# TriangleGenerator.net
KiCad netlist of a schematic drawn in EAGLE
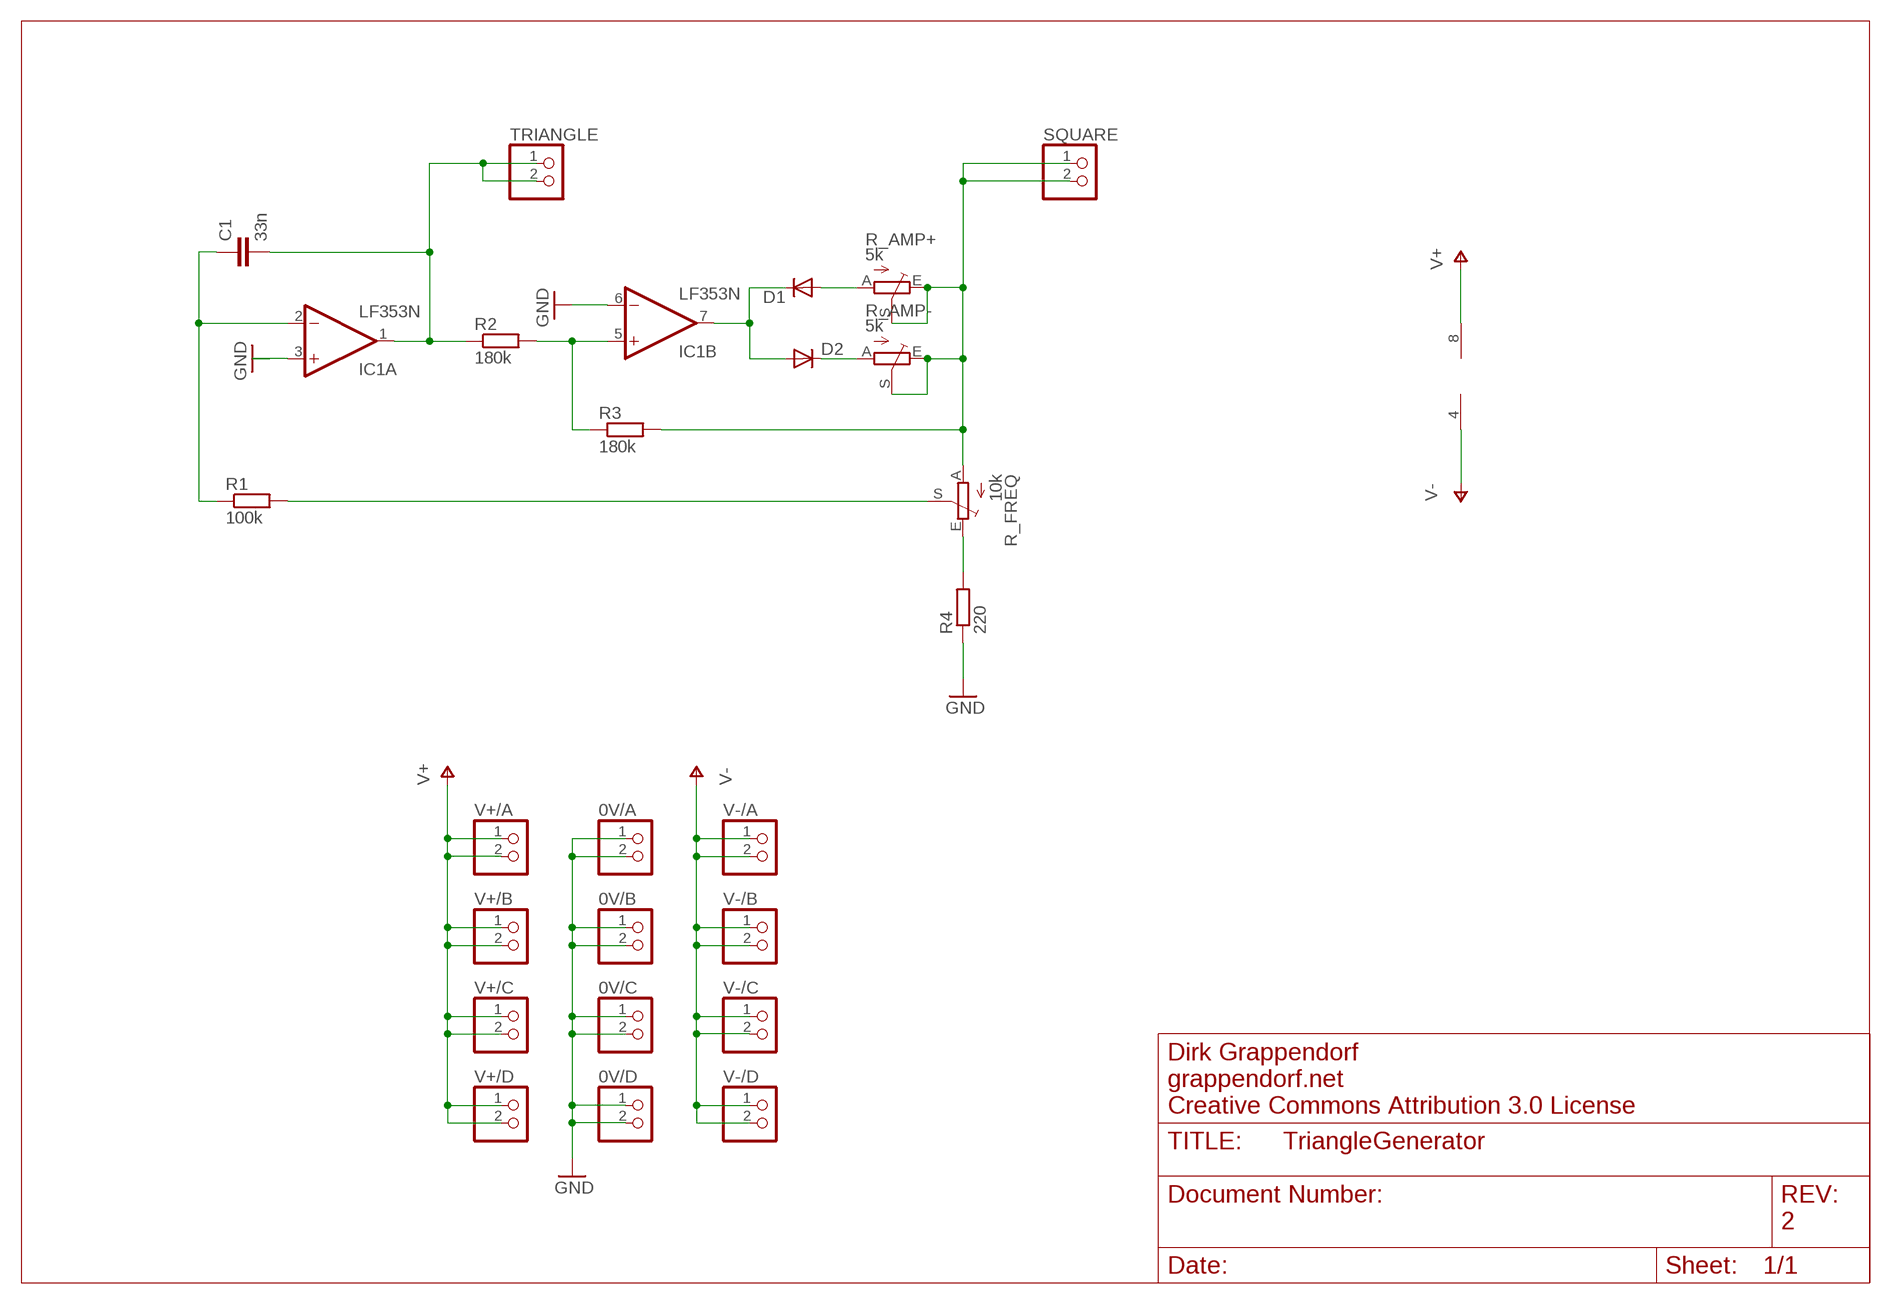
[diagram p0: schematic, sheet 1]

(export (version "E")
  (design (tool "Eeschema 10.0.6"))
  (components
    (comp (ref "0V/A")
      (value "PINHD-1X2")
      (footprint "eagle-import:1X02")
      (libsource (lib "eagle-import") (part "PINHD-1X2"))
    )
    (comp (ref "0V/B")
      (value "PINHD-1X2")
      (footprint "eagle-import:1X02")
      (libsource (lib "eagle-import") (part "PINHD-1X2"))
    )
    (comp (ref "0V/C")
      (value "PINHD-1X2")
      (footprint "eagle-import:1X02")
      (libsource (lib "eagle-import") (part "PINHD-1X2"))
    )
    (comp (ref "0V/D")
      (value "PINHD-1X2")
      (footprint "eagle-import:1X02")
      (libsource (lib "eagle-import") (part "PINHD-1X2"))
    )
    (comp (ref "C1")
      (value "33n")
      (footprint "eagle-import:C025-025X050")
      (libsource (lib "eagle-import") (part "C-EU025-025X050"))
    )
    (comp (ref "D1")
      (value "DIODE1N4148")
      (footprint "eagle-import:DIODE-1N4148")
      (libsource (lib "eagle-import") (part "DIODE1N4148"))
    )
    (comp (ref "D2")
      (value "DIODE1N4148")
      (footprint "eagle-import:DIODE-1N4148")
      (libsource (lib "eagle-import") (part "DIODE1N4148"))
    )
    (comp (ref "IC1")
      (value "LF353N")
      (footprint "eagle-import:DIL08")
      (libsource (lib "eagle-import") (part "LF353N"))
    )
    (comp (ref "R1")
      (value "100k")
      (footprint "eagle-import:0207_7")
      (libsource (lib "eagle-import") (part "R-EU_0207/7"))
    )
    (comp (ref "R2")
      (value "180k")
      (footprint "eagle-import:0207_7")
      (libsource (lib "eagle-import") (part "R-EU_0207/7"))
    )
    (comp (ref "R3")
      (value "180k")
      (footprint "eagle-import:0207_7")
      (libsource (lib "eagle-import") (part "R-EU_0207/7"))
    )
    (comp (ref "R4")
      (value "220")
      (footprint "eagle-import:0207_7")
      (libsource (lib "eagle-import") (part "R-EU_0207/7"))
    )
    (comp (ref "R_AMP+")
      (value "5k")
      (footprint "eagle-import:LI15")
      (libsource (lib "eagle-import") (part "TRIM_EU-LI15"))
    )
    (comp (ref "R_AMP-")
      (value "5k")
      (footprint "eagle-import:LI15")
      (libsource (lib "eagle-import") (part "TRIM_EU-LI15"))
    )
    (comp (ref "R_FREQ")
      (value "10k")
      (footprint "eagle-import:LI15")
      (libsource (lib "eagle-import") (part "TRIM_EU-LI15"))
    )
    (comp (ref "SQUARE")
      (value "PINHD-1X2")
      (footprint "eagle-import:1X02")
      (libsource (lib "eagle-import") (part "PINHD-1X2"))
    )
    (comp (ref "TRIANGLE")
      (value "PINHD-1X2")
      (footprint "eagle-import:1X02")
      (libsource (lib "eagle-import") (part "PINHD-1X2"))
    )
    (comp (ref "V+/A")
      (value "PINHD-1X2")
      (footprint "eagle-import:1X02")
      (libsource (lib "eagle-import") (part "PINHD-1X2"))
    )
    (comp (ref "V+/B")
      (value "PINHD-1X2")
      (footprint "eagle-import:1X02")
      (libsource (lib "eagle-import") (part "PINHD-1X2"))
    )
    (comp (ref "V+/C")
      (value "PINHD-1X2")
      (footprint "eagle-import:1X02")
      (libsource (lib "eagle-import") (part "PINHD-1X2"))
    )
    (comp (ref "V+/D")
      (value "PINHD-1X2")
      (footprint "eagle-import:1X02")
      (libsource (lib "eagle-import") (part "PINHD-1X2"))
    )
    (comp (ref "V-/A")
      (value "PINHD-1X2")
      (footprint "eagle-import:1X02")
      (libsource (lib "eagle-import") (part "PINHD-1X2"))
    )
    (comp (ref "V-/B")
      (value "PINHD-1X2")
      (footprint "eagle-import:1X02")
      (libsource (lib "eagle-import") (part "PINHD-1X2"))
    )
    (comp (ref "V-/C")
      (value "PINHD-1X2")
      (footprint "eagle-import:1X02")
      (libsource (lib "eagle-import") (part "PINHD-1X2"))
    )
    (comp (ref "V-/D")
      (value "PINHD-1X2")
      (footprint "eagle-import:1X02")
      (libsource (lib "eagle-import") (part "PINHD-1X2"))
    )
  )
  (nets
    (net (code "1") (name "GND") (class "Default")
      (node (ref "0V/A") (pin "1") (pinfunction "1_1") (pintype "passive"))
      (node (ref "0V/A") (pin "2") (pinfunction "2_2") (pintype "passive"))
      (node (ref "0V/B") (pin "1") (pinfunction "1_1") (pintype "passive"))
      (node (ref "0V/B") (pin "2") (pinfunction "2_2") (pintype "passive"))
      (node (ref "0V/C") (pin "1") (pinfunction "1_1") (pintype "passive"))
      (node (ref "0V/C") (pin "2") (pinfunction "2_2") (pintype "passive"))
      (node (ref "0V/D") (pin "1") (pinfunction "1_1") (pintype "passive"))
      (node (ref "0V/D") (pin "2") (pinfunction "2_2") (pintype "passive"))
      (node (ref "IC1") (pin "3") (pinfunction "+IN_3") (pintype "input"))
      (node (ref "IC1") (pin "6") (pinfunction "-IN_6") (pintype "input"))
      (node (ref "R4") (pin "1") (pinfunction "1_1") (pintype "passive"))
    )
    (net (code "2") (name "Net-(D1-PadA)") (class "Default")
      (node (ref "D1") (pin "A") (pinfunction "A_A") (pintype "passive"))
      (node (ref "R_AMP+") (pin "A") (pinfunction "A_A") (pintype "passive"))
    )
    (net (code "3") (name "Net-(D2-PadC)") (class "Default")
      (node (ref "D2") (pin "C") (pinfunction "C_C") (pintype "passive"))
      (node (ref "R_AMP-") (pin "A") (pinfunction "A_A") (pintype "passive"))
    )
    (net (code "4") (name "Net-(IC1A--IN)") (class "Default")
      (node (ref "C1") (pin "1") (pinfunction "1_1") (pintype "passive"))
      (node (ref "IC1") (pin "2") (pinfunction "-IN_2") (pintype "input"))
      (node (ref "R1") (pin "1") (pinfunction "1_1") (pintype "passive"))
    )
    (net (code "5") (name "Net-(IC1A-OUT)") (class "Default")
      (node (ref "C1") (pin "2") (pinfunction "2_2") (pintype "passive"))
      (node (ref "IC1") (pin "1") (pinfunction "OUT_1") (pintype "output"))
      (node (ref "R2") (pin "1") (pinfunction "1_1") (pintype "passive"))
      (node (ref "TRIANGLE") (pin "1") (pinfunction "1_1") (pintype "passive"))
      (node (ref "TRIANGLE") (pin "2") (pinfunction "2_2") (pintype "passive"))
    )
    (net (code "6") (name "Net-(IC1B-+IN)") (class "Default")
      (node (ref "IC1") (pin "5") (pinfunction "+IN_5") (pintype "input"))
      (node (ref "R2") (pin "2") (pinfunction "2_2") (pintype "passive"))
      (node (ref "R3") (pin "1") (pinfunction "1_1") (pintype "passive"))
    )
    (net (code "7") (name "Net-(IC1B-OUT)") (class "Default")
      (node (ref "D1") (pin "C") (pinfunction "C_C") (pintype "passive"))
      (node (ref "D2") (pin "A") (pinfunction "A_A") (pintype "passive"))
      (node (ref "IC1") (pin "7") (pinfunction "OUT_7") (pintype "output"))
    )
    (net (code "8") (name "Net-(R1-Pad2)") (class "Default")
      (node (ref "R1") (pin "2") (pinfunction "2_2") (pintype "passive"))
      (node (ref "R_FREQ") (pin "S") (pinfunction "S_S") (pintype "passive"))
    )
    (net (code "9") (name "Net-(R3-Pad2)") (class "Default")
      (node (ref "R3") (pin "2") (pinfunction "2_2") (pintype "passive"))
      (node (ref "R_AMP+") (pin "E") (pinfunction "E_E") (pintype "passive"))
      (node (ref "R_AMP+") (pin "S") (pinfunction "S_S") (pintype "passive"))
      (node (ref "R_AMP-") (pin "E") (pinfunction "E_E") (pintype "passive"))
      (node (ref "R_AMP-") (pin "S") (pinfunction "S_S") (pintype "passive"))
      (node (ref "R_FREQ") (pin "A") (pinfunction "A_A") (pintype "passive"))
      (node (ref "SQUARE") (pin "1") (pinfunction "1_1") (pintype "passive"))
      (node (ref "SQUARE") (pin "2") (pinfunction "2_2") (pintype "passive"))
    )
    (net (code "10") (name "Net-(R4-Pad2)") (class "Default")
      (node (ref "R4") (pin "2") (pinfunction "2_2") (pintype "passive"))
      (node (ref "R_FREQ") (pin "E") (pinfunction "E_E") (pintype "passive"))
    )
    (net (code "11") (name "V+") (class "Default")
      (node (ref "IC1") (pin "8") (pinfunction "V+_8") (pintype "power_in"))
      (node (ref "V+/A") (pin "1") (pinfunction "1_1") (pintype "passive"))
      (node (ref "V+/A") (pin "2") (pinfunction "2_2") (pintype "passive"))
      (node (ref "V+/B") (pin "1") (pinfunction "1_1") (pintype "passive"))
      (node (ref "V+/B") (pin "2") (pinfunction "2_2") (pintype "passive"))
      (node (ref "V+/C") (pin "1") (pinfunction "1_1") (pintype "passive"))
      (node (ref "V+/C") (pin "2") (pinfunction "2_2") (pintype "passive"))
      (node (ref "V+/D") (pin "1") (pinfunction "1_1") (pintype "passive"))
      (node (ref "V+/D") (pin "2") (pinfunction "2_2") (pintype "passive"))
    )
    (net (code "12") (name "V-") (class "Default")
      (node (ref "IC1") (pin "4") (pinfunction "V-_4") (pintype "power_in"))
      (node (ref "V-/A") (pin "1") (pinfunction "1_1") (pintype "passive"))
      (node (ref "V-/A") (pin "2") (pinfunction "2_2") (pintype "passive"))
      (node (ref "V-/B") (pin "1") (pinfunction "1_1") (pintype "passive"))
      (node (ref "V-/B") (pin "2") (pinfunction "2_2") (pintype "passive"))
      (node (ref "V-/C") (pin "1") (pinfunction "1_1") (pintype "passive"))
      (node (ref "V-/C") (pin "2") (pinfunction "2_2") (pintype "passive"))
      (node (ref "V-/D") (pin "1") (pinfunction "1_1") (pintype "passive"))
      (node (ref "V-/D") (pin "2") (pinfunction "2_2") (pintype "passive"))
    )
  )
)
